# displayadapter.net
KiCad netlist of a schematic drawn in EAGLE
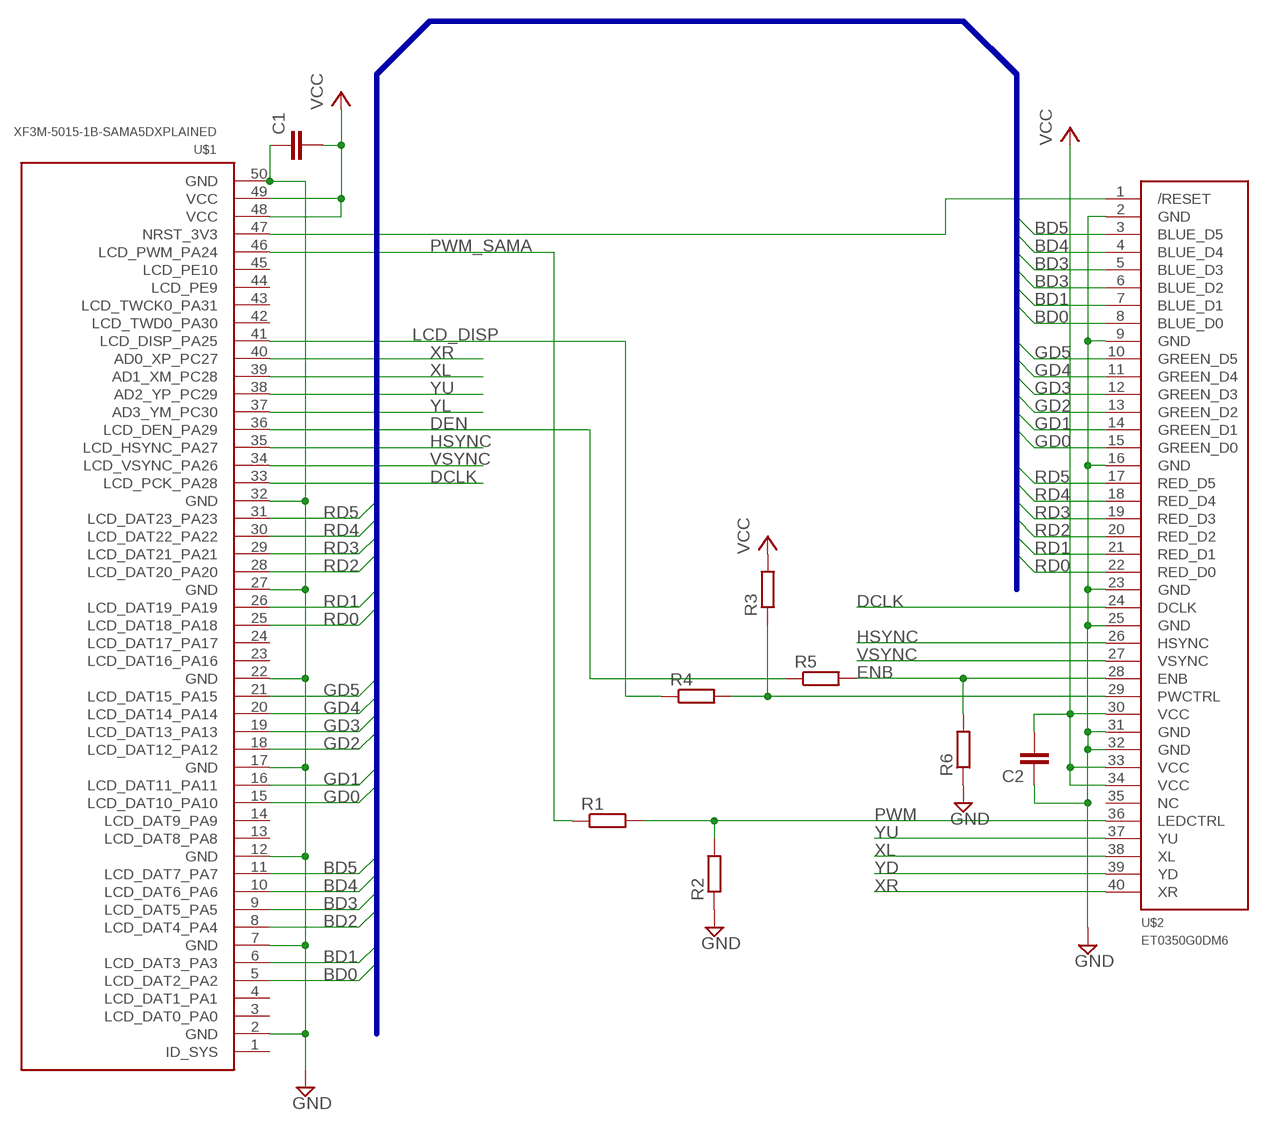
[diagram p0: schematic, sheet 1]

(export (version "E")
  (design (tool "Eeschema 10.0.6"))
  (components
    (comp (ref "C1")
      (value "C-EUC0805")
      (footprint "eagle-import:C0805")
      (libsource (lib "eagle-import") (part "C-EUC0805"))
    )
    (comp (ref "C2")
      (value "C-EUC0805")
      (footprint "eagle-import:C0805")
      (libsource (lib "eagle-import") (part "C-EUC0805"))
    )
    (comp (ref "R1")
      (value "R-EU_M0805")
      (footprint "eagle-import:M0805")
      (libsource (lib "eagle-import") (part "R-EU_M0805"))
    )
    (comp (ref "R2")
      (value "R-EU_M0805")
      (footprint "eagle-import:M0805")
      (libsource (lib "eagle-import") (part "R-EU_M0805"))
    )
    (comp (ref "R3")
      (value "R-EU_M0805")
      (footprint "eagle-import:M0805")
      (libsource (lib "eagle-import") (part "R-EU_M0805"))
    )
    (comp (ref "R4")
      (value "R-EU_M0805")
      (footprint "eagle-import:M0805")
      (libsource (lib "eagle-import") (part "R-EU_M0805"))
    )
    (comp (ref "R5")
      (value "R-EU_M0805")
      (footprint "eagle-import:M0805")
      (libsource (lib "eagle-import") (part "R-EU_M0805"))
    )
    (comp (ref "R6")
      (value "R-EU_M0805")
      (footprint "eagle-import:M0805")
      (libsource (lib "eagle-import") (part "R-EU_M0805"))
    )
    (comp (ref "U$1")
      (value "XF3M-5015-1B-SAMA5DXPLAINED")
      (footprint "eagle-import:XF3M-5015-1B")
      (libsource (lib "eagle-import") (part "XF3M-5015-1B-SAMA5DXPLAINED"))
    )
    (comp (ref "U$2")
      (value "ET0350G0DM6")
      (footprint "eagle-import:XF3M-4015-1B")
      (libsource (lib "eagle-import") (part "ET0350G0DM6"))
    )
  )
  (nets
    (net (code "1") (name "/BD0") (class "Default")
      (node (ref "U$1") (pin "5") (pinfunction "LCD_DAT2_PA2_5") (pintype "bidirectional"))
      (node (ref "U$2") (pin "8") (pinfunction "BLUE_D0_8") (pintype "input"))
    )
    (net (code "2") (name "/BD1") (class "Default")
      (node (ref "U$1") (pin "6") (pinfunction "LCD_DAT3_PA3_6") (pintype "bidirectional"))
      (node (ref "U$2") (pin "7") (pinfunction "BLUE_D1_7") (pintype "input"))
    )
    (net (code "3") (name "/BD2") (class "Default")
      (node (ref "U$1") (pin "8") (pinfunction "LCD_DAT4_PA4_8") (pintype "bidirectional"))
      (node (ref "U$2") (pin "6") (pinfunction "BLUE_D2_6") (pintype "input"))
    )
    (net (code "4") (name "/BD3") (class "Default")
      (node (ref "U$1") (pin "9") (pinfunction "LCD_DAT5_PA5_9") (pintype "bidirectional"))
      (node (ref "U$2") (pin "5") (pinfunction "BLUE_D3_5") (pintype "input"))
    )
    (net (code "5") (name "/BD4") (class "Default")
      (node (ref "U$1") (pin "10") (pinfunction "LCD_DAT6_PA6_10") (pintype "bidirectional"))
      (node (ref "U$2") (pin "4") (pinfunction "BLUE_D4_4") (pintype "input"))
    )
    (net (code "6") (name "/BD5") (class "Default")
      (node (ref "U$1") (pin "11") (pinfunction "LCD_DAT7_PA7_11") (pintype "bidirectional"))
      (node (ref "U$2") (pin "3") (pinfunction "BLUE_D5_3") (pintype "input"))
    )
    (net (code "7") (name "/DCLK") (class "Default")
      (node (ref "U$1") (pin "33") (pinfunction "LCD_PCK_PA28_33") (pintype "bidirectional"))
      (node (ref "U$2") (pin "24") (pinfunction "DCLK_24") (pintype "bidirectional"))
    )
    (net (code "8") (name "/DEN") (class "Default")
      (node (ref "R5") (pin "1") (pinfunction "1_1") (pintype "passive"))
      (node (ref "U$1") (pin "36") (pinfunction "LCD_DEN_PA29_36") (pintype "bidirectional"))
    )
    (net (code "9") (name "/ENB") (class "Default")
      (node (ref "R5") (pin "2") (pinfunction "2_2") (pintype "passive"))
      (node (ref "R6") (pin "2") (pinfunction "2_2") (pintype "passive"))
      (node (ref "U$2") (pin "28") (pinfunction "ENB_28") (pintype "input"))
    )
    (net (code "10") (name "/GD0") (class "Default")
      (node (ref "U$1") (pin "15") (pinfunction "LCD_DAT10_PA10_15") (pintype "bidirectional"))
      (node (ref "U$2") (pin "15") (pinfunction "GREEN_D0_15") (pintype "input"))
    )
    (net (code "11") (name "/GD1") (class "Default")
      (node (ref "U$1") (pin "16") (pinfunction "LCD_DAT11_PA11_16") (pintype "bidirectional"))
      (node (ref "U$2") (pin "14") (pinfunction "GREEN_D1_14") (pintype "input"))
    )
    (net (code "12") (name "/GD2") (class "Default")
      (node (ref "U$1") (pin "18") (pinfunction "LCD_DAT12_PA12_18") (pintype "bidirectional"))
      (node (ref "U$2") (pin "13") (pinfunction "GREEN_D2_13") (pintype "input"))
    )
    (net (code "13") (name "/GD3") (class "Default")
      (node (ref "U$1") (pin "19") (pinfunction "LCD_DAT13_PA13_19") (pintype "bidirectional"))
      (node (ref "U$2") (pin "12") (pinfunction "GREEN_D3_12") (pintype "input"))
    )
    (net (code "14") (name "/GD4") (class "Default")
      (node (ref "U$1") (pin "20") (pinfunction "LCD_DAT14_PA14_20") (pintype "bidirectional"))
      (node (ref "U$2") (pin "11") (pinfunction "GREEN_D4_11") (pintype "input"))
    )
    (net (code "15") (name "/GD5") (class "Default")
      (node (ref "U$1") (pin "21") (pinfunction "LCD_DAT15_PA15_21") (pintype "bidirectional"))
      (node (ref "U$2") (pin "10") (pinfunction "GREEN_D5_10") (pintype "input"))
    )
    (net (code "16") (name "/HSYNC") (class "Default")
      (node (ref "U$1") (pin "35") (pinfunction "LCD_HSYNC_PA27_35") (pintype "bidirectional"))
      (node (ref "U$2") (pin "26") (pinfunction "HSYNC_26") (pintype "input"))
    )
    (net (code "17") (name "/LCD_DISP") (class "Default")
      (node (ref "R4") (pin "1") (pinfunction "1_1") (pintype "passive"))
      (node (ref "U$1") (pin "41") (pinfunction "LCD_DISP_PA25_41") (pintype "bidirectional"))
    )
    (net (code "18") (name "/PWM") (class "Default")
      (node (ref "R1") (pin "2") (pinfunction "2_2") (pintype "passive"))
      (node (ref "R2") (pin "2") (pinfunction "2_2") (pintype "passive"))
      (node (ref "U$2") (pin "36") (pinfunction "LEDCTRL_36") (pintype "input"))
    )
    (net (code "19") (name "/PWM_SAMA") (class "Default")
      (node (ref "R1") (pin "1") (pinfunction "1_1") (pintype "passive"))
      (node (ref "U$1") (pin "46") (pinfunction "LCD_PWM_PA24_46") (pintype "bidirectional"))
    )
    (net (code "20") (name "/RD0") (class "Default")
      (node (ref "U$1") (pin "25") (pinfunction "LCD_DAT18_PA18_25") (pintype "bidirectional"))
      (node (ref "U$2") (pin "22") (pinfunction "RED_D0_22") (pintype "input"))
    )
    (net (code "21") (name "/RD1") (class "Default")
      (node (ref "U$1") (pin "26") (pinfunction "LCD_DAT19_PA19_26") (pintype "bidirectional"))
      (node (ref "U$2") (pin "21") (pinfunction "RED_D1_21") (pintype "input"))
    )
    (net (code "22") (name "/RD2") (class "Default")
      (node (ref "U$1") (pin "28") (pinfunction "LCD_DAT20_PA20_28") (pintype "bidirectional"))
      (node (ref "U$2") (pin "20") (pinfunction "RED_D2_20") (pintype "input"))
    )
    (net (code "23") (name "/RD3") (class "Default")
      (node (ref "U$1") (pin "29") (pinfunction "LCD_DAT21_PA21_29") (pintype "bidirectional"))
      (node (ref "U$2") (pin "19") (pinfunction "RED_D3_19") (pintype "input"))
    )
    (net (code "24") (name "/RD4") (class "Default")
      (node (ref "U$1") (pin "30") (pinfunction "LCD_DAT22_PA22_30") (pintype "bidirectional"))
      (node (ref "U$2") (pin "18") (pinfunction "RED_D4_18") (pintype "input"))
    )
    (net (code "25") (name "/RD5") (class "Default")
      (node (ref "U$1") (pin "31") (pinfunction "LCD_DAT23_PA23_31") (pintype "bidirectional"))
      (node (ref "U$2") (pin "17") (pinfunction "RED_D5_17") (pintype "input"))
    )
    (net (code "26") (name "/VSYNC") (class "Default")
      (node (ref "U$1") (pin "34") (pinfunction "LCD_VSYNC_PA26_34") (pintype "bidirectional"))
      (node (ref "U$2") (pin "27") (pinfunction "VSYNC_27") (pintype "input"))
    )
    (net (code "27") (name "/XL") (class "Default")
      (node (ref "U$1") (pin "39") (pinfunction "AD1_XM_PC28_39") (pintype "bidirectional"))
      (node (ref "U$2") (pin "38") (pinfunction "XL_38") (pintype "passive"))
    )
    (net (code "28") (name "/XR") (class "Default")
      (node (ref "U$1") (pin "40") (pinfunction "AD0_XP_PC27_40") (pintype "bidirectional"))
      (node (ref "U$2") (pin "40") (pinfunction "XR_40") (pintype "passive"))
    )
    (net (code "29") (name "/YD") (class "Default")
      (node (ref "U$2") (pin "39") (pinfunction "YD_39") (pintype "passive"))
    )
    (net (code "30") (name "/YL") (class "Default")
      (node (ref "U$1") (pin "37") (pinfunction "AD3_YM_PC30_37") (pintype "bidirectional"))
    )
    (net (code "31") (name "/YU") (class "Default")
      (node (ref "U$1") (pin "38") (pinfunction "AD2_YP_PC29_38") (pintype "bidirectional"))
      (node (ref "U$2") (pin "37") (pinfunction "YU_37") (pintype "passive"))
    )
    (net (code "32") (name "GND") (class "Default")
      (node (ref "C1") (pin "1") (pinfunction "1_1") (pintype "passive"))
      (node (ref "C2") (pin "1") (pinfunction "1_1") (pintype "passive"))
      (node (ref "R2") (pin "1") (pinfunction "1_1") (pintype "passive"))
      (node (ref "R6") (pin "1") (pinfunction "1_1") (pintype "passive"))
      (node (ref "U$1") (pin "12") (pinfunction "GND_12") (pintype "bidirectional"))
      (node (ref "U$1") (pin "17") (pinfunction "GND_17") (pintype "bidirectional"))
      (node (ref "U$1") (pin "2") (pinfunction "GND_2") (pintype "bidirectional"))
      (node (ref "U$1") (pin "22") (pinfunction "GND_22") (pintype "bidirectional"))
      (node (ref "U$1") (pin "27") (pinfunction "GND_27") (pintype "bidirectional"))
      (node (ref "U$1") (pin "32") (pinfunction "GND_32") (pintype "bidirectional"))
      (node (ref "U$1") (pin "50") (pinfunction "GND_50") (pintype "bidirectional"))
      (node (ref "U$1") (pin "7") (pinfunction "GND_7") (pintype "bidirectional"))
      (node (ref "U$2") (pin "16") (pinfunction "GND_16") (pintype "power_in"))
      (node (ref "U$2") (pin "2") (pinfunction "GND_2") (pintype "power_in"))
      (node (ref "U$2") (pin "23") (pinfunction "GND_23") (pintype "power_in"))
      (node (ref "U$2") (pin "25") (pinfunction "GND_25") (pintype "power_in"))
      (node (ref "U$2") (pin "31") (pinfunction "GND_31") (pintype "power_in"))
      (node (ref "U$2") (pin "32") (pinfunction "GND_32") (pintype "power_in"))
      (node (ref "U$2") (pin "9") (pinfunction "GND_9") (pintype "power_in"))
    )
    (net (code "33") (name "Net-(U$1-NRST_3V3)") (class "Default")
      (node (ref "U$1") (pin "47") (pinfunction "NRST_3V3_47") (pintype "bidirectional"))
      (node (ref "U$2") (pin "1") (pinfunction "/RESET_1") (pintype "input"))
    )
    (net (code "34") (name "Net-(U$2-PWCTRL)") (class "Default")
      (node (ref "R3") (pin "1") (pinfunction "1_1") (pintype "passive"))
      (node (ref "R4") (pin "2") (pinfunction "2_2") (pintype "passive"))
      (node (ref "U$2") (pin "29") (pinfunction "PWCTRL_29") (pintype "input"))
    )
    (net (code "35") (name "VCC") (class "Default")
      (node (ref "C1") (pin "2") (pinfunction "2_2") (pintype "passive"))
      (node (ref "C2") (pin "2") (pinfunction "2_2") (pintype "passive"))
      (node (ref "R3") (pin "2") (pinfunction "2_2") (pintype "passive"))
      (node (ref "U$1") (pin "48") (pinfunction "VCC_48") (pintype "power_in"))
      (node (ref "U$1") (pin "49") (pinfunction "VCC_49") (pintype "power_in"))
      (node (ref "U$2") (pin "30") (pinfunction "VCC_30") (pintype "power_in"))
      (node (ref "U$2") (pin "33") (pinfunction "VCC_33") (pintype "power_in"))
      (node (ref "U$2") (pin "34") (pinfunction "VCC_34") (pintype "power_in"))
    )
    (net (code "36") (name "unconnected-(U$1-ID_SYS-Pad1)") (class "Default")
      (node (ref "U$1") (pin "1") (pinfunction "ID_SYS_1") (pintype "input"))
    )
    (net (code "37") (name "unconnected-(U$1-LCD_DAT0_PA0-Pad3)") (class "Default")
      (node (ref "U$1") (pin "3") (pinfunction "LCD_DAT0_PA0_3") (pintype "bidirectional"))
    )
    (net (code "38") (name "unconnected-(U$1-LCD_DAT1_PA1-Pad4)") (class "Default")
      (node (ref "U$1") (pin "4") (pinfunction "LCD_DAT1_PA1_4") (pintype "bidirectional"))
    )
    (net (code "39") (name "unconnected-(U$1-LCD_DAT8_PA8-Pad13)") (class "Default")
      (node (ref "U$1") (pin "13") (pinfunction "LCD_DAT8_PA8_13") (pintype "bidirectional"))
    )
    (net (code "40") (name "unconnected-(U$1-LCD_DAT9_PA9-Pad14)") (class "Default")
      (node (ref "U$1") (pin "14") (pinfunction "LCD_DAT9_PA9_14") (pintype "bidirectional"))
    )
    (net (code "41") (name "unconnected-(U$1-LCD_DAT16_PA16-Pad23)") (class "Default")
      (node (ref "U$1") (pin "23") (pinfunction "LCD_DAT16_PA16_23") (pintype "bidirectional"))
    )
    (net (code "42") (name "unconnected-(U$1-LCD_DAT17_PA17-Pad24)") (class "Default")
      (node (ref "U$1") (pin "24") (pinfunction "LCD_DAT17_PA17_24") (pintype "bidirectional"))
    )
    (net (code "43") (name "unconnected-(U$1-LCD_PE9-Pad44)") (class "Default")
      (node (ref "U$1") (pin "44") (pinfunction "LCD_PE9_44") (pintype "bidirectional"))
    )
    (net (code "44") (name "unconnected-(U$1-LCD_PE10-Pad45)") (class "Default")
      (node (ref "U$1") (pin "45") (pinfunction "LCD_PE10_45") (pintype "bidirectional"))
    )
    (net (code "45") (name "unconnected-(U$1-LCD_TWCK0_PA31-Pad43)") (class "Default")
      (node (ref "U$1") (pin "43") (pinfunction "LCD_TWCK0_PA31_43") (pintype "bidirectional"))
    )
    (net (code "46") (name "unconnected-(U$1-LCD_TWD0_PA30-Pad42)") (class "Default")
      (node (ref "U$1") (pin "42") (pinfunction "LCD_TWD0_PA30_42") (pintype "bidirectional"))
    )
    (net (code "47") (name "unconnected-(U$2-NC-Pad35)") (class "Default")
      (node (ref "U$2") (pin "35") (pinfunction "NC_35") (pintype "no_connect"))
    )
  )
)
